# CamLight.net
KiCad netlist of a schematic drawn in EAGLE
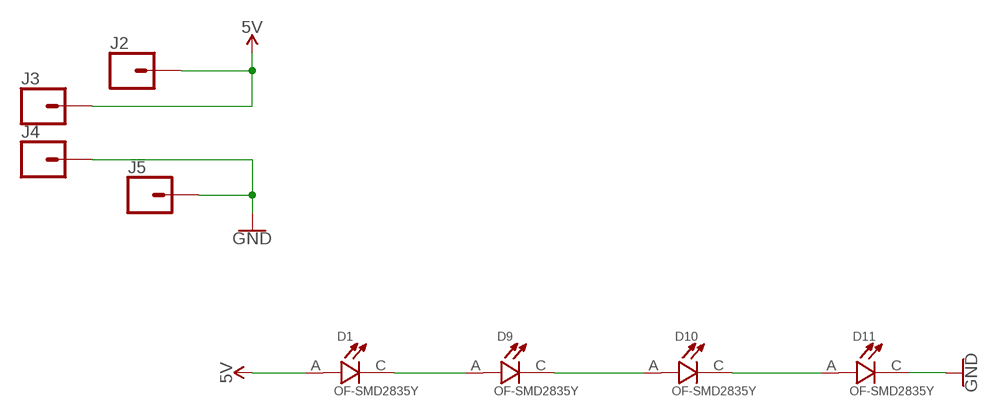
[diagram p0: schematic, sheet 1]

(export (version "E")
  (design (tool "Eeschema 10.0.6"))
  (components
    (comp (ref "D1")
      (value "OF-SMD2835Y")
      (footprint "eagle-import:LED_OF-SMD2835Y")
      (fields (field (name "MF") "Optoflash"))
      (libsource (lib "eagle-import") (part "OF-SMD2835Y"))
    )
    (comp (ref "D9")
      (value "OF-SMD2835Y")
      (footprint "eagle-import:LED_OF-SMD2835Y")
      (fields (field (name "MF") "Optoflash"))
      (libsource (lib "eagle-import") (part "OF-SMD2835Y"))
    )
    (comp (ref "D10")
      (value "OF-SMD2835Y")
      (footprint "eagle-import:LED_OF-SMD2835Y")
      (fields (field (name "MF") "Optoflash"))
      (libsource (lib "eagle-import") (part "OF-SMD2835Y"))
    )
    (comp (ref "D11")
      (value "OF-SMD2835Y")
      (footprint "eagle-import:LED_OF-SMD2835Y")
      (fields (field (name "MF") "Optoflash"))
      (libsource (lib "eagle-import") (part "OF-SMD2835Y"))
    )
    (comp (ref "J2")
      (value "CONN_01")
      (footprint "eagle-import:1X01")
      (libsource (lib "eagle-import") (part "CONN_01"))
    )
    (comp (ref "J3")
      (value "CONN_01")
      (footprint "eagle-import:1X01")
      (libsource (lib "eagle-import") (part "CONN_01"))
    )
    (comp (ref "J4")
      (value "CONN_01")
      (footprint "eagle-import:1X01")
      (libsource (lib "eagle-import") (part "CONN_01"))
    )
    (comp (ref "J5")
      (value "CONN_01")
      (footprint "eagle-import:1X01")
      (libsource (lib "eagle-import") (part "CONN_01"))
    )
  )
  (nets
    (net (code "1") (name "5V") (class "Default")
      (node (ref "D1") (pin "A") (pinfunction "A_A") (pintype "passive"))
      (node (ref "J2") (pin "1") (pinfunction "1_1") (pintype "passive"))
      (node (ref "J3") (pin "1") (pinfunction "1_1") (pintype "passive"))
    )
    (net (code "2") (name "GND") (class "Default")
      (node (ref "D11") (pin "C") (pinfunction "C_C") (pintype "passive"))
      (node (ref "J4") (pin "1") (pinfunction "1_1") (pintype "passive"))
      (node (ref "J5") (pin "1") (pinfunction "1_1") (pintype "passive"))
    )
    (net (code "3") (name "Net-(D1-PadC)") (class "Default")
      (node (ref "D1") (pin "C") (pinfunction "C_C") (pintype "passive"))
      (node (ref "D9") (pin "A") (pinfunction "A_A") (pintype "passive"))
    )
    (net (code "4") (name "Net-(D10-PadA)") (class "Default")
      (node (ref "D10") (pin "A") (pinfunction "A_A") (pintype "passive"))
      (node (ref "D9") (pin "C") (pinfunction "C_C") (pintype "passive"))
    )
    (net (code "5") (name "Net-(D10-PadC)") (class "Default")
      (node (ref "D10") (pin "C") (pinfunction "C_C") (pintype "passive"))
      (node (ref "D11") (pin "A") (pinfunction "A_A") (pintype "passive"))
    )
  )
)
